# FWR.net
KiCad netlist of a schematic drawn in EAGLE
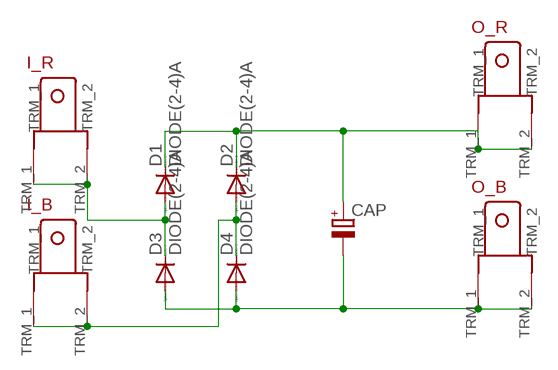
[diagram p0: schematic, sheet 1]

(export (version "E")
  (design (tool "Eeschema 10.0.6"))
  (components
    (comp (ref "CAP")
      (value "CAP_POL")
      (footprint "eagle-import:E3,5-8")
      (libsource (lib "eagle-import") (part "CAP_POL"))
    )
    (comp (ref "D1")
      (value "DIODE(2-4)A")
      (footprint "eagle-import:DO35-10")
      (libsource (lib "eagle-import") (part "DIODE(2-4)A"))
    )
    (comp (ref "D2")
      (value "DIODE(2-4)A")
      (footprint "eagle-import:DO35-10")
      (libsource (lib "eagle-import") (part "DIODE(2-4)A"))
    )
    (comp (ref "D3")
      (value "DIODE(2-4)A")
      (footprint "eagle-import:DO35-10")
      (libsource (lib "eagle-import") (part "DIODE(2-4)A"))
    )
    (comp (ref "D4")
      (value "DIODE(2-4)A")
      (footprint "eagle-import:DO35-10")
      (libsource (lib "eagle-import") (part "DIODE(2-4)A"))
    )
    (comp (ref "I_B")
      (value "TERMINAL_EDITED")
      (footprint "eagle-import:TERMINAL_EDITED")
      (libsource (lib "eagle-import") (part "TERMINAL_EDITED"))
    )
    (comp (ref "I_R")
      (value "TERMINAL_EDITED")
      (footprint "eagle-import:TERMINAL_EDITED")
      (libsource (lib "eagle-import") (part "TERMINAL_EDITED"))
    )
    (comp (ref "O_B")
      (value "TERMINAL_EDITED")
      (footprint "eagle-import:TERMINAL_EDITED")
      (libsource (lib "eagle-import") (part "TERMINAL_EDITED"))
    )
    (comp (ref "O_R")
      (value "TERMINAL_EDITED")
      (footprint "eagle-import:TERMINAL_EDITED")
      (libsource (lib "eagle-import") (part "TERMINAL_EDITED"))
    )
  )
  (nets
    (net (code "1") (name "Net-(CAP-Pad+)") (class "Default")
      (node (ref "CAP") (pin "+") (pinfunction "+_+") (pintype "passive"))
      (node (ref "D1") (pin "C") (pinfunction "C_C") (pintype "passive"))
      (node (ref "D2") (pin "C") (pinfunction "C_C") (pintype "passive"))
      (node (ref "O_R") (pin "TRM_1") (pinfunction "TRM_1_TRM_1") (pintype "bidirectional"))
      (node (ref "O_R") (pin "TRM_2") (pinfunction "TRM_2_TRM_2") (pintype "bidirectional"))
    )
    (net (code "2") (name "Net-(CAP-Pad-)") (class "Default")
      (node (ref "CAP") (pin "-") (pinfunction "-_-") (pintype "passive"))
      (node (ref "D3") (pin "A") (pinfunction "A_A") (pintype "passive"))
      (node (ref "D4") (pin "A") (pinfunction "A_A") (pintype "passive"))
      (node (ref "O_B") (pin "TRM_1") (pinfunction "TRM_1_TRM_1") (pintype "bidirectional"))
      (node (ref "O_B") (pin "TRM_2") (pinfunction "TRM_2_TRM_2") (pintype "bidirectional"))
    )
    (net (code "3") (name "Net-(D1-PadA)") (class "Default")
      (node (ref "D1") (pin "A") (pinfunction "A_A") (pintype "passive"))
      (node (ref "D3") (pin "C") (pinfunction "C_C") (pintype "passive"))
      (node (ref "I_R") (pin "TRM_1") (pinfunction "TRM_1_TRM_1") (pintype "bidirectional"))
      (node (ref "I_R") (pin "TRM_2") (pinfunction "TRM_2_TRM_2") (pintype "bidirectional"))
    )
    (net (code "4") (name "Net-(D2-PadA)") (class "Default")
      (node (ref "D2") (pin "A") (pinfunction "A_A") (pintype "passive"))
      (node (ref "D4") (pin "C") (pinfunction "C_C") (pintype "passive"))
      (node (ref "I_B") (pin "TRM_1") (pinfunction "TRM_1_TRM_1") (pintype "bidirectional"))
      (node (ref "I_B") (pin "TRM_2") (pinfunction "TRM_2_TRM_2") (pintype "bidirectional"))
    )
  )
)
